# Orange_Suffocomp.net
KiCad netlist of a schematic drawn in EAGLE
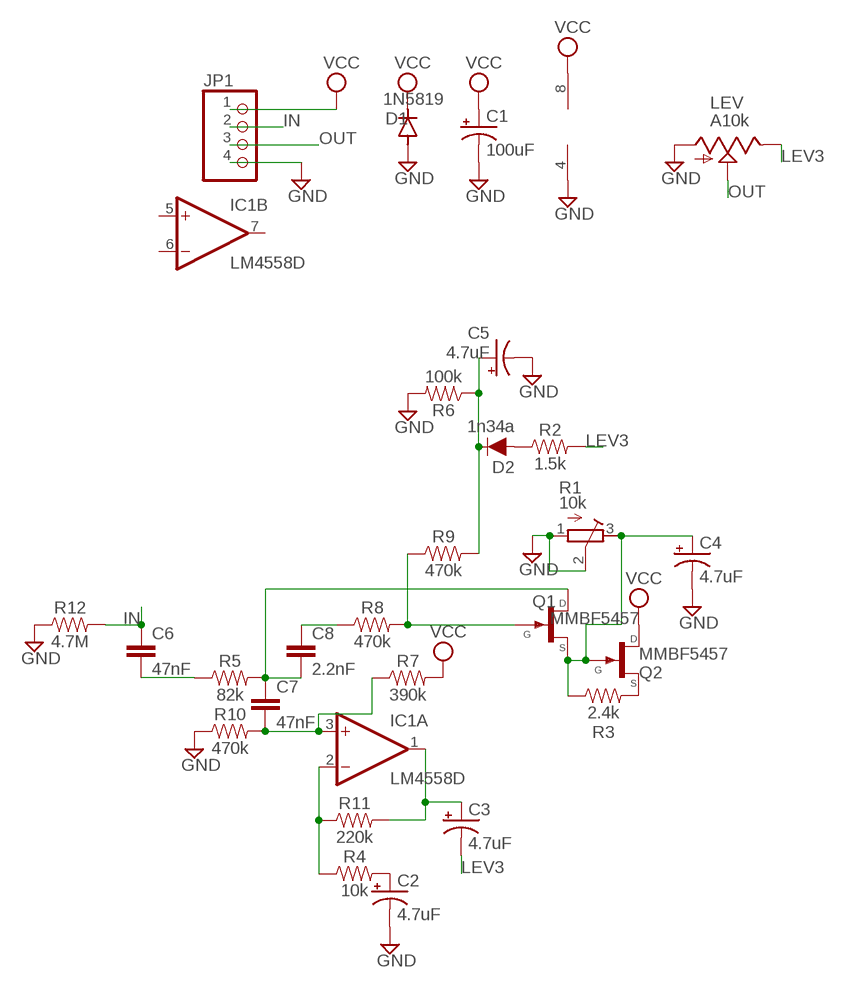
[diagram p0: schematic, sheet 1]

(export (version "E")
  (design (tool "Eeschema 10.0.6"))
  (components
    (comp (ref "C1")
      (value "100uF")
      (footprint "eagle-import:PAN_B_SMD+THRU")
      (libsource (lib "eagle-import") (part "CAP_SMD+THRUPAN_B"))
    )
    (comp (ref "C2")
      (value "4.7uF")
      (footprint "eagle-import:PAN_B_SMD+THRU")
      (libsource (lib "eagle-import") (part "CAP_SMD+THRUPAN_B"))
    )
    (comp (ref "C3")
      (value "4.7uF")
      (footprint "eagle-import:PAN_B_SMD+THRU")
      (libsource (lib "eagle-import") (part "CAP_SMD+THRUPAN_B"))
    )
    (comp (ref "C4")
      (value "4.7uF")
      (footprint "eagle-import:PAN_B_SMD+THRU")
      (libsource (lib "eagle-import") (part "CAP_SMD+THRUPAN_B"))
    )
    (comp (ref "C5")
      (value "4.7uF")
      (footprint "eagle-import:PAN_B_SMD+THRU")
      (libsource (lib "eagle-import") (part "CAP_SMD+THRUPAN_B"))
    )
    (comp (ref "C6")
      (value "47nF")
      (footprint "eagle-import:0603")
      (libsource (lib "eagle-import") (part "47NF-0603-25V-5%"))
    )
    (comp (ref "C7")
      (value "47nF")
      (footprint "eagle-import:0603")
      (libsource (lib "eagle-import") (part "47NF-0603-25V-5%"))
    )
    (comp (ref "C8")
      (value "2.2nF")
      (footprint "eagle-import:0603")
      (libsource (lib "eagle-import") (part "2.2NF/2200PF-0603-50V-10%"))
    )
    (comp (ref "D1")
      (value "1N5819")
      (footprint "eagle-import:SOD123")
      (libsource (lib "eagle-import") (part "DIODE-SOD123"))
    )
    (comp (ref "D2")
      (value "1n34a")
      (footprint "eagle-import:DIODE-1N4148")
      (libsource (lib "eagle-import") (part "DIODE-1N4148"))
    )
    (comp (ref "IC1")
      (value "LM4558D")
      (footprint "eagle-import:SO08")
      (libsource (lib "eagle-import") (part "4558DLM"))
    )
    (comp (ref "JP1")
      (value "PINHD-1X4")
      (footprint "eagle-import:1X04")
      (libsource (lib "eagle-import") (part "PINHD-1X4"))
    )
    (comp (ref "LEV")
      (value "A10k")
      (footprint "eagle-import:9MM_SNAP-IN_POT")
      (libsource (lib "eagle-import") (part "9MM_SNAP-IN_POT_"))
    )
    (comp (ref "Q1")
      (value "MMBF5457")
      (footprint "eagle-import:SOT23")
      (fields (field (name "MF") "ON Semiconductor"))
      (libsource (lib "eagle-import") (part "MMBF5457"))
    )
    (comp (ref "Q2")
      (value "MMBF5457")
      (footprint "eagle-import:SOT23")
      (fields (field (name "MF") "ON Semiconductor"))
      (libsource (lib "eagle-import") (part "MMBF5457"))
    )
    (comp (ref "R1")
      (value "10k")
      (footprint "eagle-import:RTRIM3296W")
      (libsource (lib "eagle-import") (part "R-TRIMM3296W"))
    )
    (comp (ref "R2")
      (value "1.5k")
      (footprint "eagle-import:0603")
      (libsource (lib "eagle-import") (part "1.5KOHM-0603-1/10W-1%"))
    )
    (comp (ref "R3")
      (value "2.4k")
      (footprint "eagle-import:0603")
      (libsource (lib "eagle-import") (part "2.49KOHM-0603-1/10W-1%"))
    )
    (comp (ref "R4")
      (value "10k")
      (footprint "eagle-import:0603")
      (libsource (lib "eagle-import") (part "10KOHM-0603-1/10W-1%"))
    )
    (comp (ref "R5")
      (value "82k")
      (footprint "eagle-import:0603")
      (libsource (lib "eagle-import") (part "82OHM-0603-1/10W-1%"))
    )
    (comp (ref "R6")
      (value "100k")
      (footprint "eagle-import:0603")
      (libsource (lib "eagle-import") (part "100KOHM-0603-1/10W-1%"))
    )
    (comp (ref "R7")
      (value "390k")
      (footprint "eagle-import:0603")
      (libsource (lib "eagle-import") (part "390KOHM-0603-1/10W-1%"))
    )
    (comp (ref "R8")
      (value "470k")
      (footprint "eagle-import:0603")
      (libsource (lib "eagle-import") (part "470OHM-0603-1/10W-1%"))
    )
    (comp (ref "R9")
      (value "470k")
      (footprint "eagle-import:0603")
      (libsource (lib "eagle-import") (part "470OHM-0603-1/10W-1%"))
    )
    (comp (ref "R10")
      (value "470k")
      (footprint "eagle-import:0603")
      (libsource (lib "eagle-import") (part "470OHM-0603-1/10W-1%"))
    )
    (comp (ref "R11")
      (value "220k")
      (footprint "eagle-import:0603")
      (libsource (lib "eagle-import") (part "220KOHM-0603-1/10W-1%"))
    )
    (comp (ref "R12")
      (value "4.7M")
      (footprint "eagle-import:0603")
      (libsource (lib "eagle-import") (part "4.7KOHM-0603-1/10W-1%"))
    )
  )
  (nets
    (net (code "1") (name "/IN") (class "Default")
      (node (ref "C6") (pin "1") (pinfunction "1_1") (pintype "passive"))
      (node (ref "JP1") (pin "2") (pinfunction "2_2") (pintype "passive"))
      (node (ref "R12") (pin "2") (pinfunction "2_2") (pintype "passive"))
    )
    (net (code "2") (name "/LEV3") (class "Default")
      (node (ref "C3") (pin "-") (pinfunction "-_-") (pintype "passive"))
      (node (ref "C3") (pin "--") (pinfunction "-_--") (pintype "passive"))
      (node (ref "LEV") (pin "3") (pinfunction "E_3") (pintype "passive"))
      (node (ref "R2") (pin "2") (pinfunction "2_2") (pintype "passive"))
    )
    (net (code "3") (name "/OUT") (class "Default")
      (node (ref "JP1") (pin "3") (pinfunction "3_3") (pintype "passive"))
      (node (ref "LEV") (pin "2") (pinfunction "S_2") (pintype "passive"))
    )
    (net (code "4") (name "GND") (class "Default")
      (node (ref "C1") (pin "-") (pinfunction "-_-") (pintype "passive"))
      (node (ref "C1") (pin "--") (pinfunction "-_--") (pintype "passive"))
      (node (ref "C2") (pin "-") (pinfunction "-_-") (pintype "passive"))
      (node (ref "C2") (pin "--") (pinfunction "-_--") (pintype "passive"))
      (node (ref "C4") (pin "-") (pinfunction "-_-") (pintype "passive"))
      (node (ref "C4") (pin "--") (pinfunction "-_--") (pintype "passive"))
      (node (ref "C5") (pin "-") (pinfunction "-_-") (pintype "passive"))
      (node (ref "C5") (pin "--") (pinfunction "-_--") (pintype "passive"))
      (node (ref "D1") (pin "A") (pinfunction "A_A") (pintype "passive"))
      (node (ref "IC1") (pin "4") (pinfunction "V-_4") (pintype "power_in"))
      (node (ref "JP1") (pin "4") (pinfunction "4_4") (pintype "passive"))
      (node (ref "LEV") (pin "1") (pinfunction "A_1") (pintype "passive"))
      (node (ref "R1") (pin "1") (pinfunction "A_1") (pintype "passive"))
      (node (ref "R1") (pin "2") (pinfunction "S_2") (pintype "passive"))
      (node (ref "R10") (pin "1") (pinfunction "1_1") (pintype "passive"))
      (node (ref "R12") (pin "1") (pinfunction "1_1") (pintype "passive"))
      (node (ref "R6") (pin "2") (pinfunction "2_2") (pintype "passive"))
    )
    (net (code "5") (name "Net-(C2-+-Pad++)") (class "Default")
      (node (ref "C2") (pin "+") (pinfunction "+_+") (pintype "passive"))
      (node (ref "C2") (pin "++") (pinfunction "+_++") (pintype "passive"))
      (node (ref "R4") (pin "2") (pinfunction "2_2") (pintype "passive"))
    )
    (net (code "6") (name "Net-(C5-+-Pad++)") (class "Default")
      (node (ref "C5") (pin "+") (pinfunction "+_+") (pintype "passive"))
      (node (ref "C5") (pin "++") (pinfunction "+_++") (pintype "passive"))
      (node (ref "D2") (pin "C") (pinfunction "C_C") (pintype "passive"))
      (node (ref "R6") (pin "1") (pinfunction "1_1") (pintype "passive"))
      (node (ref "R9") (pin "2") (pinfunction "2_2") (pintype "passive"))
    )
    (net (code "7") (name "Net-(C6-Pad2)") (class "Default")
      (node (ref "C6") (pin "2") (pinfunction "2_2") (pintype "passive"))
      (node (ref "R5") (pin "1") (pinfunction "1_1") (pintype "passive"))
    )
    (net (code "8") (name "Net-(C8-Pad1)") (class "Default")
      (node (ref "C8") (pin "1") (pinfunction "1_1") (pintype "passive"))
      (node (ref "R8") (pin "1") (pinfunction "1_1") (pintype "passive"))
    )
    (net (code "9") (name "Net-(D2-PadA)") (class "Default")
      (node (ref "D2") (pin "A") (pinfunction "A_A") (pintype "passive"))
      (node (ref "R2") (pin "1") (pinfunction "1_1") (pintype "passive"))
    )
    (net (code "10") (name "Net-(IC1A-+IN)") (class "Default")
      (node (ref "C7") (pin "2") (pinfunction "2_2") (pintype "passive"))
      (node (ref "IC1") (pin "3") (pinfunction "+IN_3") (pintype "input"))
      (node (ref "R10") (pin "2") (pinfunction "2_2") (pintype "passive"))
      (node (ref "R7") (pin "1") (pinfunction "1_1") (pintype "passive"))
    )
    (net (code "11") (name "Net-(IC1A--IN)") (class "Default")
      (node (ref "IC1") (pin "2") (pinfunction "-IN_2") (pintype "input"))
      (node (ref "R11") (pin "1") (pinfunction "1_1") (pintype "passive"))
      (node (ref "R4") (pin "1") (pinfunction "1_1") (pintype "passive"))
    )
    (net (code "12") (name "Net-(IC1A-OUT)") (class "Default")
      (node (ref "C3") (pin "+") (pinfunction "+_+") (pintype "passive"))
      (node (ref "C3") (pin "++") (pinfunction "+_++") (pintype "passive"))
      (node (ref "IC1") (pin "1") (pinfunction "OUT_1") (pintype "output"))
      (node (ref "R11") (pin "2") (pinfunction "2_2") (pintype "passive"))
    )
    (net (code "13") (name "Net-(Q1-D)") (class "Default")
      (node (ref "C7") (pin "1") (pinfunction "1_1") (pintype "passive"))
      (node (ref "C8") (pin "2") (pinfunction "2_2") (pintype "passive"))
      (node (ref "Q1") (pin "1") (pinfunction "D_1") (pintype "passive"))
      (node (ref "R5") (pin "2") (pinfunction "2_2") (pintype "passive"))
    )
    (net (code "14") (name "Net-(Q1-G)") (class "Default")
      (node (ref "Q1") (pin "3") (pinfunction "G_3") (pintype "passive"))
      (node (ref "R8") (pin "2") (pinfunction "2_2") (pintype "passive"))
      (node (ref "R9") (pin "1") (pinfunction "1_1") (pintype "passive"))
    )
    (net (code "15") (name "Net-(Q1-S)") (class "Default")
      (node (ref "C4") (pin "+") (pinfunction "+_+") (pintype "passive"))
      (node (ref "C4") (pin "++") (pinfunction "+_++") (pintype "passive"))
      (node (ref "Q1") (pin "2") (pinfunction "S_2") (pintype "passive"))
      (node (ref "Q2") (pin "3") (pinfunction "G_3") (pintype "passive"))
      (node (ref "R1") (pin "3") (pinfunction "E_3") (pintype "passive"))
      (node (ref "R3") (pin "1") (pinfunction "1_1") (pintype "passive"))
    )
    (net (code "16") (name "Net-(Q2-S)") (class "Default")
      (node (ref "Q2") (pin "2") (pinfunction "S_2") (pintype "passive"))
      (node (ref "R3") (pin "2") (pinfunction "2_2") (pintype "passive"))
    )
    (net (code "17") (name "VCC") (class "Default")
      (node (ref "C1") (pin "+") (pinfunction "+_+") (pintype "passive"))
      (node (ref "C1") (pin "++") (pinfunction "+_++") (pintype "passive"))
      (node (ref "D1") (pin "C") (pinfunction "C_C") (pintype "passive"))
      (node (ref "IC1") (pin "8") (pinfunction "V+_8") (pintype "power_in"))
      (node (ref "JP1") (pin "1") (pinfunction "1_1") (pintype "passive"))
      (node (ref "Q2") (pin "1") (pinfunction "D_1") (pintype "passive"))
      (node (ref "R7") (pin "2") (pinfunction "2_2") (pintype "passive"))
    )
    (net (code "18") (name "unconnected-(IC1B-+IN-Pad5)") (class "Default")
      (node (ref "IC1") (pin "5") (pinfunction "+IN_5") (pintype "input"))
    )
    (net (code "19") (name "unconnected-(IC1B--IN-Pad6)") (class "Default")
      (node (ref "IC1") (pin "6") (pinfunction "-IN_6") (pintype "input"))
    )
    (net (code "20") (name "unconnected-(IC1B-OUT-Pad7)") (class "Default")
      (node (ref "IC1") (pin "7") (pinfunction "OUT_7") (pintype "output"))
    )
  )
)
